# NIRGM_V4.net
KiCad netlist of a schematic drawn in EAGLE
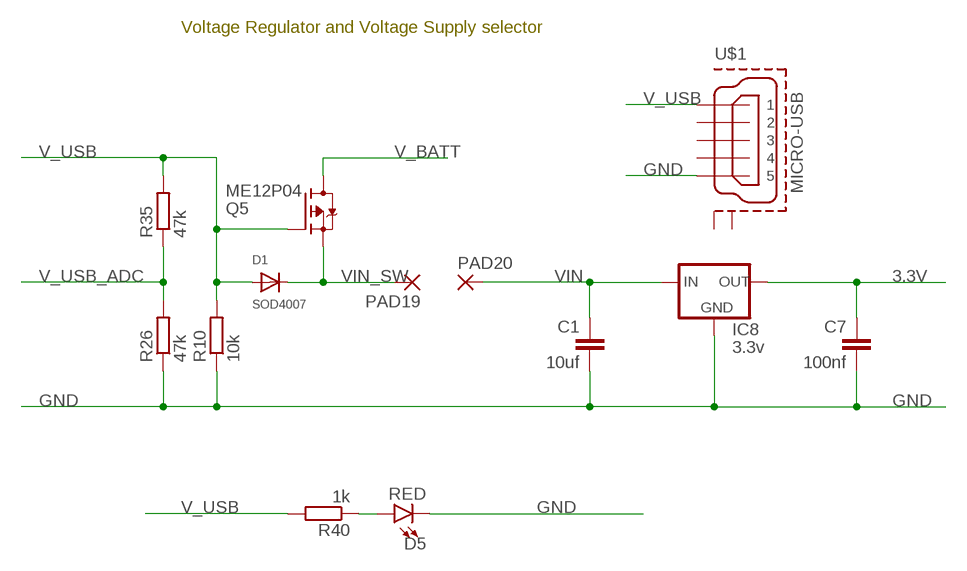
[diagram p0: schematic, sheet 1]
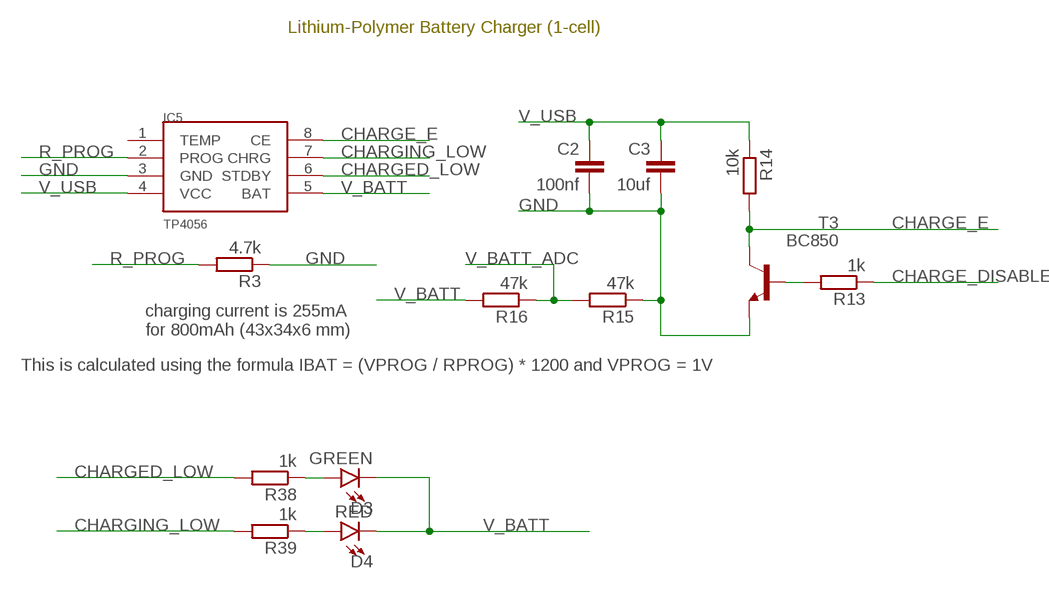
[diagram p1: schematic, sheet 2]
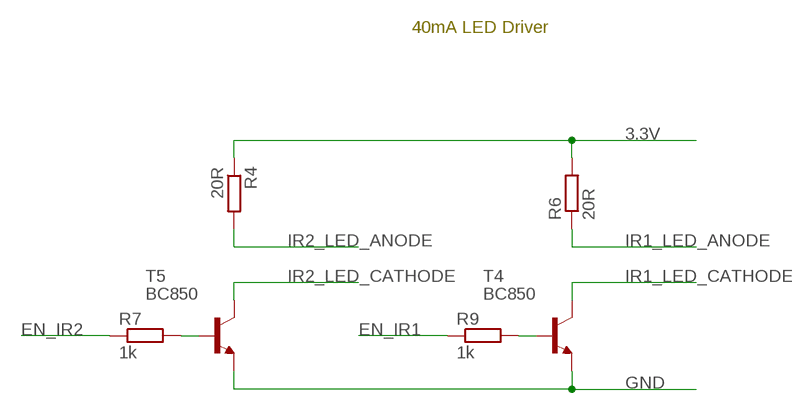
[diagram p2: schematic, sheet 3]
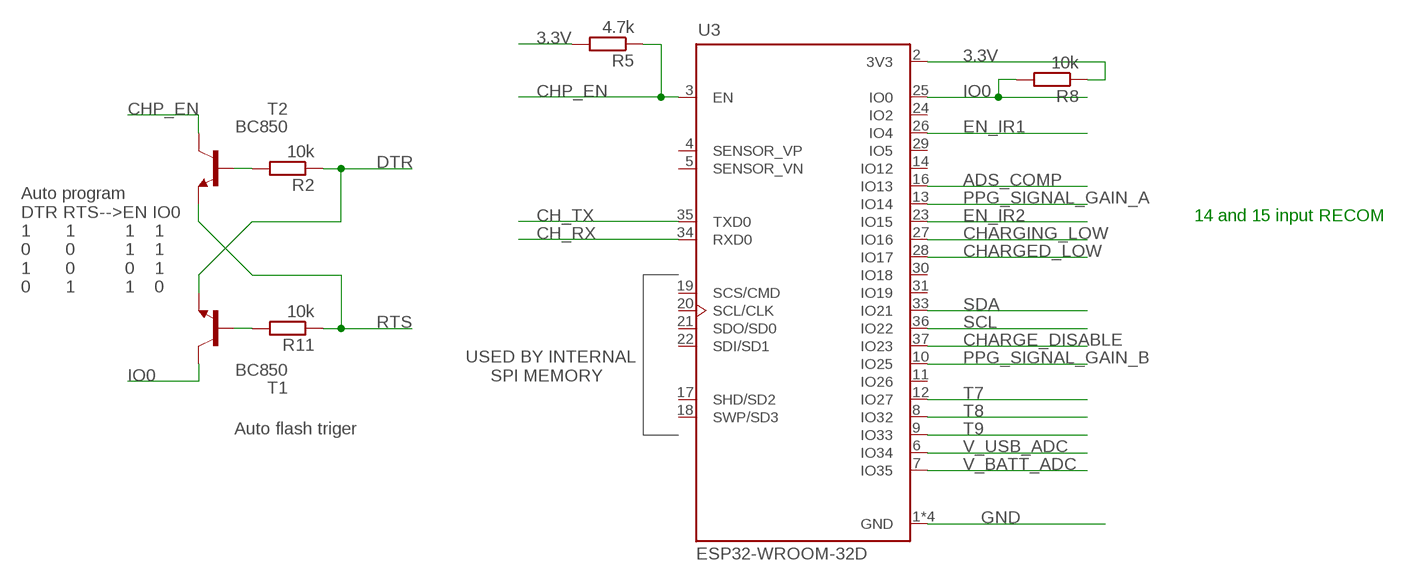
[diagram p3: schematic, sheet 4]
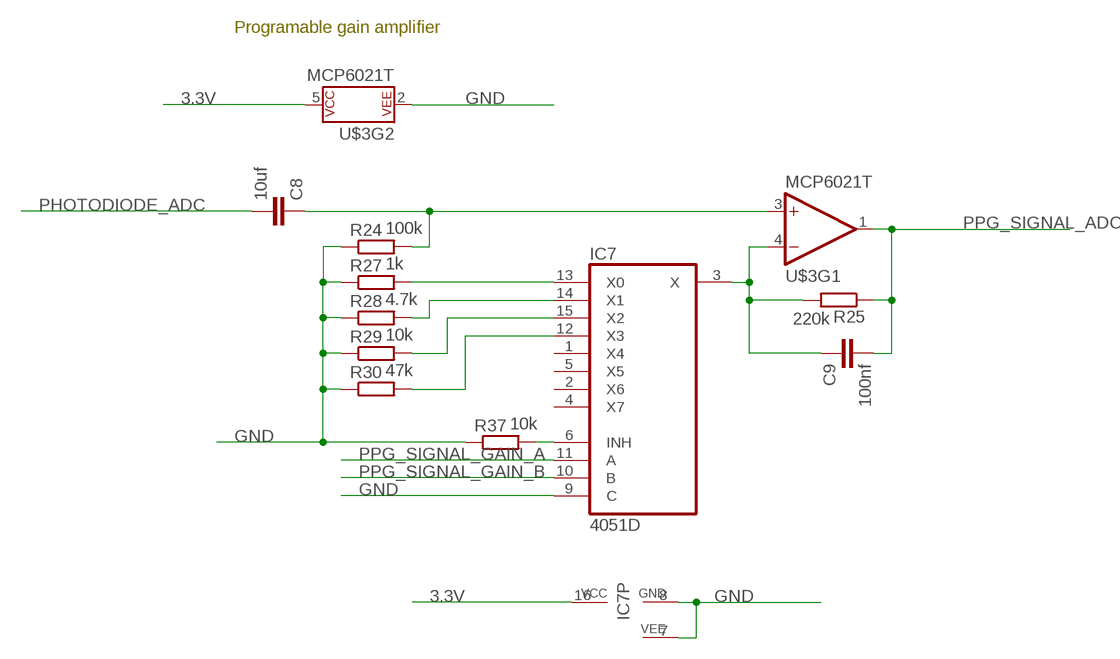
[diagram p4: schematic, sheet 5]
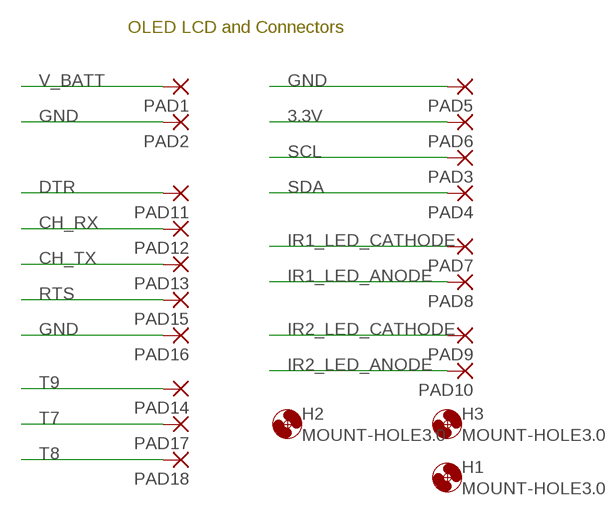
[diagram p5: schematic, sheet 6]
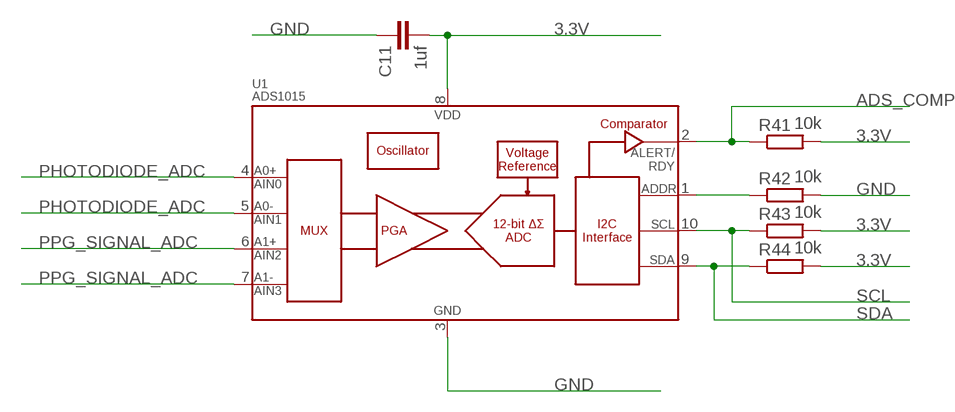
[diagram p6: schematic, sheet 7]
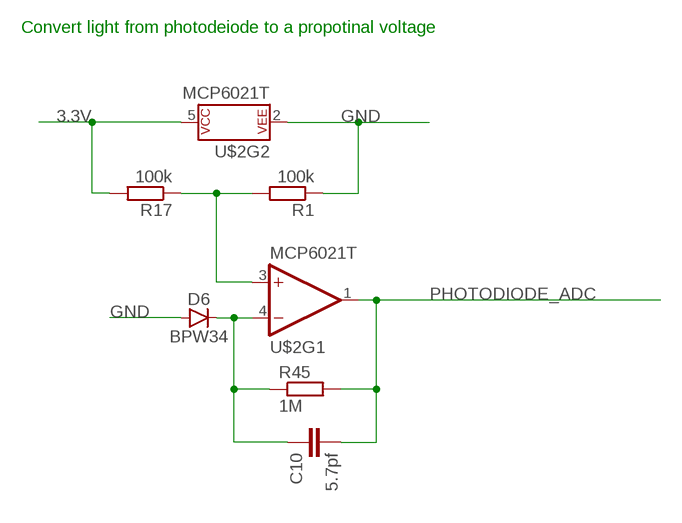
[diagram p7: schematic, sheet 8]

(export (version "E")
  (design (tool "Eeschema 10.0.6"))
  (components
    (comp (ref "H1")
      (value "MOUNT-HOLE3.0")
      (footprint "eagle-import:3,0")
      (libsource (lib "eagle-import") (part "MOUNT-HOLE3.0"))
    )
    (comp (ref "H2")
      (value "MOUNT-HOLE3.0")
      (footprint "eagle-import:3,0")
      (libsource (lib "eagle-import") (part "MOUNT-HOLE3.0"))
    )
    (comp (ref "H3")
      (value "MOUNT-HOLE3.0")
      (footprint "eagle-import:3,0")
      (libsource (lib "eagle-import") (part "MOUNT-HOLE3.0"))
    )
    (comp (ref "PAD1")
      (value "WIREPADSMD5-2,5")
      (footprint "eagle-import:5-2,5")
      (libsource (lib "eagle-import") (part "WIREPADSMD5-2,5"))
    )
    (comp (ref "PAD2")
      (value "WIREPADSMD5-2,5")
      (footprint "eagle-import:5-2,5")
      (libsource (lib "eagle-import") (part "WIREPADSMD5-2,5"))
    )
    (comp (ref "PAD3")
      (value "SMD2")
      (footprint "eagle-import:SMD1,27-2,54")
      (libsource (lib "eagle-import") (part "SMD2"))
    )
    (comp (ref "PAD4")
      (value "SMD2")
      (footprint "eagle-import:SMD1,27-2,54")
      (libsource (lib "eagle-import") (part "SMD2"))
    )
    (comp (ref "PAD5")
      (value "SMD2")
      (footprint "eagle-import:SMD1,27-2,54")
      (libsource (lib "eagle-import") (part "SMD2"))
    )
    (comp (ref "PAD6")
      (value "SMD2")
      (footprint "eagle-import:SMD1,27-2,54")
      (libsource (lib "eagle-import") (part "SMD2"))
    )
    (comp (ref "PAD7")
      (value "SMD2")
      (footprint "eagle-import:SMD1,27-2,54")
      (libsource (lib "eagle-import") (part "SMD2"))
    )
    (comp (ref "PAD8")
      (value "SMD2")
      (footprint "eagle-import:SMD1,27-2,54")
      (libsource (lib "eagle-import") (part "SMD2"))
    )
    (comp (ref "PAD9")
      (value "SMD2")
      (footprint "eagle-import:SMD1,27-2,54")
      (libsource (lib "eagle-import") (part "SMD2"))
    )
    (comp (ref "PAD10")
      (value "SMD2")
      (footprint "eagle-import:SMD1,27-2,54")
      (libsource (lib "eagle-import") (part "SMD2"))
    )
    (comp (ref "PAD11")
      (value "SMD2")
      (footprint "eagle-import:SMD1,27-2,54")
      (libsource (lib "eagle-import") (part "SMD2"))
    )
    (comp (ref "PAD12")
      (value "SMD2")
      (footprint "eagle-import:SMD1,27-2,54")
      (libsource (lib "eagle-import") (part "SMD2"))
    )
    (comp (ref "PAD13")
      (value "SMD2")
      (footprint "eagle-import:SMD1,27-2,54")
      (libsource (lib "eagle-import") (part "SMD2"))
    )
    (comp (ref "PAD14")
      (value "SMD2")
      (footprint "eagle-import:SMD1,27-2,54")
      (libsource (lib "eagle-import") (part "SMD2"))
    )
    (comp (ref "PAD15")
      (value "SMD2")
      (footprint "eagle-import:SMD1,27-2,54")
      (libsource (lib "eagle-import") (part "SMD2"))
    )
    (comp (ref "PAD16")
      (value "SMD2")
      (footprint "eagle-import:SMD1,27-2,54")
      (libsource (lib "eagle-import") (part "SMD2"))
    )
    (comp (ref "PAD17")
      (value "SMD2")
      (footprint "eagle-import:SMD1,27-2,54")
      (libsource (lib "eagle-import") (part "SMD2"))
    )
    (comp (ref "PAD18")
      (value "SMD2")
      (footprint "eagle-import:SMD1,27-2,54")
      (libsource (lib "eagle-import") (part "SMD2"))
    )
    (comp (ref "C1")
      (value "10uf")
      (footprint "eagle-import:C1206K")
      (libsource (lib "eagle-import") (part "C-EUC1206K"))
    )
    (comp (ref "C7")
      (value "100nf")
      (footprint "eagle-import:C1206K")
      (libsource (lib "eagle-import") (part "C-EUC1206K"))
    )
    (comp (ref "D1")
      (value "SOD4007")
      (footprint "eagle-import:SOD-123FL")
      (libsource (lib "eagle-import") (part "DIODE_SOD-123FL"))
    )
    (comp (ref "D5")
      (value "RED")
      (footprint "eagle-import:LED-1206")
      (libsource (lib "eagle-import") (part "LED-GREEN1206"))
    )
    (comp (ref "IC8")
      (value "3.3v")
      (footprint "eagle-import:TO252")
      (libsource (lib "eagle-import") (part "LM1117TO252"))
    )
    (comp (ref "PAD19")
      (value "SMD2")
      (footprint "eagle-import:SMD1,27-2,54")
      (libsource (lib "eagle-import") (part "SMD2"))
    )
    (comp (ref "PAD20")
      (value "SMD2")
      (footprint "eagle-import:SMD1,27-2,54")
      (libsource (lib "eagle-import") (part "SMD2"))
    )
    (comp (ref "Q5")
      (value "ME12P04")
      (footprint "eagle-import:TO252")
      (libsource (lib "eagle-import") (part "FDD4141TO252"))
    )
    (comp (ref "R10")
      (value "10k")
      (footprint "eagle-import:R1206")
      (libsource (lib "eagle-import") (part "R-EU_R1206"))
    )
    (comp (ref "R26")
      (value "47k")
      (footprint "eagle-import:R1206")
      (libsource (lib "eagle-import") (part "R-EU_R1206"))
    )
    (comp (ref "R35")
      (value "47k")
      (footprint "eagle-import:R1206")
      (libsource (lib "eagle-import") (part "R-EU_R1206"))
    )
    (comp (ref "R40")
      (value "1k")
      (footprint "eagle-import:R1206")
      (libsource (lib "eagle-import") (part "R-EU_R1206"))
    )
    (comp (ref "U$1")
      (value "MICRO-USB")
      (footprint "eagle-import:47589-0001")
      (libsource (lib "eagle-import") (part "MICRO-USB-RECEPTACLE47589-0001"))
    )
    (comp (ref "C10")
      (value "5.7pf")
      (footprint "eagle-import:C1206K")
      (libsource (lib "eagle-import") (part "C-EUC1206K"))
    )
    (comp (ref "D6")
      (value "BPW34")
      (footprint "eagle-import:BPW34")
      (libsource (lib "eagle-import") (part "BPW34"))
    )
    (comp (ref "R1")
      (value "100k")
      (footprint "eagle-import:R1206")
      (libsource (lib "eagle-import") (part "R-EU_R1206"))
    )
    (comp (ref "R17")
      (value "100k")
      (footprint "eagle-import:R1206")
      (libsource (lib "eagle-import") (part "R-EU_R1206"))
    )
    (comp (ref "R45")
      (value "1M")
      (footprint "eagle-import:R1206")
      (libsource (lib "eagle-import") (part "R-EU_R1206"))
    )
    (comp (ref "U$2")
      (value "MCP6021T")
      (footprint "eagle-import:SOT23-5")
      (libsource (lib "eagle-import") (part "MCP6021T-E/OT"))
    )
    (comp (ref "C2")
      (value "100nf")
      (footprint "eagle-import:C1206K")
      (libsource (lib "eagle-import") (part "C-EUC1206K"))
    )
    (comp (ref "C3")
      (value "10uf")
      (footprint "eagle-import:C1206K")
      (libsource (lib "eagle-import") (part "C-EUC1206K"))
    )
    (comp (ref "D3")
      (value "GREEN")
      (footprint "eagle-import:LED-1206")
      (libsource (lib "eagle-import") (part "LED-GREEN1206"))
    )
    (comp (ref "D4")
      (value "RED")
      (footprint "eagle-import:LED-1206")
      (libsource (lib "eagle-import") (part "LED-GREEN1206"))
    )
    (comp (ref "IC5")
      (value "TP4056")
      (footprint "eagle-import:SOP-8")
      (libsource (lib "eagle-import") (part "TP4056"))
    )
    (comp (ref "R3")
      (value "4.7k")
      (footprint "eagle-import:R1206")
      (libsource (lib "eagle-import") (part "R-EU_R1206"))
    )
    (comp (ref "R13")
      (value "1k")
      (footprint "eagle-import:R1206")
      (libsource (lib "eagle-import") (part "R-EU_R1206"))
    )
    (comp (ref "R14")
      (value "10k")
      (footprint "eagle-import:R1206")
      (libsource (lib "eagle-import") (part "R-EU_R1206"))
    )
    (comp (ref "R15")
      (value "47k")
      (footprint "eagle-import:R1206")
      (libsource (lib "eagle-import") (part "R-EU_R1206"))
    )
    (comp (ref "R16")
      (value "47k")
      (footprint "eagle-import:R1206")
      (libsource (lib "eagle-import") (part "R-EU_R1206"))
    )
    (comp (ref "R38")
      (value "1k")
      (footprint "eagle-import:R1206")
      (libsource (lib "eagle-import") (part "R-EU_R1206"))
    )
    (comp (ref "R39")
      (value "1k")
      (footprint "eagle-import:R1206")
      (libsource (lib "eagle-import") (part "R-EU_R1206"))
    )
    (comp (ref "T3")
      (value "BC850")
      (footprint "eagle-import:SOT23")
      (libsource (lib "eagle-import") (part "BC850"))
    )
    (comp (ref "C11")
      (value "1uf")
      (footprint "eagle-import:C1206K")
      (libsource (lib "eagle-import") (part "C-EUC1206K"))
    )
    (comp (ref "R41")
      (value "10k")
      (footprint "eagle-import:R1206")
      (libsource (lib "eagle-import") (part "R-EU_R1206"))
    )
    (comp (ref "R42")
      (value "10k")
      (footprint "eagle-import:R1206")
      (libsource (lib "eagle-import") (part "R-EU_R1206"))
    )
    (comp (ref "R43")
      (value "10k")
      (footprint "eagle-import:R1206")
      (libsource (lib "eagle-import") (part "R-EU_R1206"))
    )
    (comp (ref "R44")
      (value "10k")
      (footprint "eagle-import:R1206")
      (libsource (lib "eagle-import") (part "R-EU_R1206"))
    )
    (comp (ref "U1")
      (value "ADS1015")
      (footprint "eagle-import:MSOP10")
      (libsource (lib "eagle-import") (part "ADS1015"))
    )
    (comp (ref "R2")
      (value "10k")
      (footprint "eagle-import:R1206")
      (libsource (lib "eagle-import") (part "R-EU_R1206"))
    )
    (comp (ref "R5")
      (value "4.7k")
      (footprint "eagle-import:R1206")
      (libsource (lib "eagle-import") (part "R-EU_R1206"))
    )
    (comp (ref "R8")
      (value "10k")
      (footprint "eagle-import:R1206")
      (libsource (lib "eagle-import") (part "R-EU_R1206"))
    )
    (comp (ref "R11")
      (value "10k")
      (footprint "eagle-import:R1206")
      (libsource (lib "eagle-import") (part "R-EU_R1206"))
    )
    (comp (ref "T1")
      (value "BC850")
      (footprint "eagle-import:SOT23")
      (libsource (lib "eagle-import") (part "BC850"))
    )
    (comp (ref "T2")
      (value "BC850")
      (footprint "eagle-import:SOT23")
      (libsource (lib "eagle-import") (part "BC850"))
    )
    (comp (ref "U3")
      (value "ESP32-WROOM-32D")
      (footprint "eagle-import:MODULE_ESP32-WROOM-32D")
      (fields (field (name "MF") "Espressif Systems"))
      (libsource (lib "eagle-import") (part "ESP32-WROOM-32D"))
    )
    (comp (ref "R4")
      (value "20R")
      (footprint "eagle-import:R1206")
      (libsource (lib "eagle-import") (part "R-EU_R1206"))
    )
    (comp (ref "R6")
      (value "20R")
      (footprint "eagle-import:R1206")
      (libsource (lib "eagle-import") (part "R-EU_R1206"))
    )
    (comp (ref "R7")
      (value "1k")
      (footprint "eagle-import:R1206")
      (libsource (lib "eagle-import") (part "R-EU_R1206"))
    )
    (comp (ref "R9")
      (value "1k")
      (footprint "eagle-import:R1206")
      (libsource (lib "eagle-import") (part "R-EU_R1206"))
    )
    (comp (ref "T4")
      (value "BC850")
      (footprint "eagle-import:SOT23")
      (libsource (lib "eagle-import") (part "BC850"))
    )
    (comp (ref "T5")
      (value "BC850")
      (footprint "eagle-import:SOT23")
      (libsource (lib "eagle-import") (part "BC850"))
    )
    (comp (ref "C8")
      (value "10uf")
      (footprint "eagle-import:C1206K")
      (libsource (lib "eagle-import") (part "C-EUC1206K"))
    )
    (comp (ref "C9")
      (value "100nf")
      (footprint "eagle-import:C1206K")
      (libsource (lib "eagle-import") (part "C-EUC1206K"))
    )
    (comp (ref "IC7")
      (value "4051D")
      (footprint "eagle-import:SO16")
      (libsource (lib "eagle-import") (part "4051D"))
    )
    (comp (ref "R24")
      (value "100k")
      (footprint "eagle-import:R1206")
      (libsource (lib "eagle-import") (part "R-EU_R1206"))
    )
    (comp (ref "R25")
      (value "220k")
      (footprint "eagle-import:R1206")
      (libsource (lib "eagle-import") (part "R-EU_R1206"))
    )
    (comp (ref "R27")
      (value "1k")
      (footprint "eagle-import:R1206")
      (libsource (lib "eagle-import") (part "R-EU_R1206"))
    )
    (comp (ref "R28")
      (value "4.7k")
      (footprint "eagle-import:R1206")
      (libsource (lib "eagle-import") (part "R-EU_R1206"))
    )
    (comp (ref "R29")
      (value "10k")
      (footprint "eagle-import:R1206")
      (libsource (lib "eagle-import") (part "R-EU_R1206"))
    )
    (comp (ref "R30")
      (value "47k")
      (footprint "eagle-import:R1206")
      (libsource (lib "eagle-import") (part "R-EU_R1206"))
    )
    (comp (ref "R37")
      (value "10k")
      (footprint "eagle-import:R1206")
      (libsource (lib "eagle-import") (part "R-EU_R1206"))
    )
    (comp (ref "U$3")
      (value "MCP6021T")
      (footprint "eagle-import:SOT23-5")
      (libsource (lib "eagle-import") (part "MCP6021T-E/OT"))
    )
  )
  (nets
    (net (code "1") (name "3.3V") (class "Default")
      (node (ref "C11") (pin "2") (pinfunction "2_2") (pintype "passive"))
      (node (ref "C7") (pin "1") (pinfunction "1_1") (pintype "passive"))
      (node (ref "IC7") (pin "16") (pinfunction "VCC_16") (pintype "power_in"))
      (node (ref "IC8") (pin "3") (pinfunction "OUT_3") (pintype "passive"))
      (node (ref "PAD6") (pin "1") (pinfunction "P_1") (pintype "passive"))
      (node (ref "R17") (pin "2") (pinfunction "2_2") (pintype "passive"))
      (node (ref "R4") (pin "1") (pinfunction "1_1") (pintype "passive"))
      (node (ref "R41") (pin "2") (pinfunction "2_2") (pintype "passive"))
      (node (ref "R43") (pin "2") (pinfunction "2_2") (pintype "passive"))
      (node (ref "R44") (pin "2") (pinfunction "2_2") (pintype "passive"))
      (node (ref "R5") (pin "2") (pinfunction "2_2") (pintype "passive"))
      (node (ref "R6") (pin "2") (pinfunction "2_2") (pintype "passive"))
      (node (ref "R8") (pin "1") (pinfunction "1_1") (pintype "passive"))
      (node (ref "U$2") (pin "5") (pinfunction "P$V+_5") (pintype "bidirectional"))
      (node (ref "U$3") (pin "5") (pinfunction "P$V+_5") (pintype "bidirectional"))
      (node (ref "U1") (pin "8") (pinfunction "VDD_8") (pintype "bidirectional"))
      (node (ref "U3") (pin "2") (pinfunction "3V3_2") (pintype "power_in"))
    )
    (net (code "2") (name "ADS_COMP") (class "Default")
      (node (ref "R41") (pin "1") (pinfunction "1_1") (pintype "passive"))
      (node (ref "U1") (pin "2") (pinfunction "ALERT/RDY_2") (pintype "bidirectional"))
      (node (ref "U3") (pin "16") (pinfunction "IO13_16") (pintype "bidirectional"))
    )
    (net (code "3") (name "CHARGED_LOW") (class "Default")
      (node (ref "IC5") (pin "6") (pinfunction "STDBY_6") (pintype "bidirectional"))
      (node (ref "R38") (pin "2") (pinfunction "2_2") (pintype "passive"))
      (node (ref "U3") (pin "28") (pinfunction "IO17_28") (pintype "bidirectional"))
    )
    (net (code "4") (name "CHARGE_DISABLE") (class "Default")
      (node (ref "R13") (pin "1") (pinfunction "1_1") (pintype "passive"))
      (node (ref "U3") (pin "37") (pinfunction "IO23_37") (pintype "bidirectional"))
    )
    (net (code "5") (name "CHARGE_E") (class "Default")
      (node (ref "IC5") (pin "8") (pinfunction "CE_8") (pintype "bidirectional"))
      (node (ref "R14") (pin "2") (pinfunction "2_2") (pintype "passive"))
      (node (ref "T3") (pin "3") (pinfunction "C_3") (pintype "passive"))
    )
    (net (code "6") (name "CHARGING_LOW") (class "Default")
      (node (ref "IC5") (pin "7") (pinfunction "CHRG_7") (pintype "bidirectional"))
      (node (ref "R39") (pin "2") (pinfunction "2_2") (pintype "passive"))
      (node (ref "U3") (pin "27") (pinfunction "IO16_27") (pintype "bidirectional"))
    )
    (net (code "7") (name "CHP_EN") (class "Default")
      (node (ref "R5") (pin "1") (pinfunction "1_1") (pintype "passive"))
      (node (ref "T2") (pin "3") (pinfunction "C_3") (pintype "passive"))
      (node (ref "U3") (pin "3") (pinfunction "EN_3") (pintype "input"))
    )
    (net (code "8") (name "CH_RX") (class "Default")
      (node (ref "PAD12") (pin "1") (pinfunction "P_1") (pintype "passive"))
      (node (ref "U3") (pin "34") (pinfunction "RXD0_34") (pintype "bidirectional"))
    )
    (net (code "9") (name "CH_TX") (class "Default")
      (node (ref "PAD13") (pin "1") (pinfunction "P_1") (pintype "passive"))
      (node (ref "U3") (pin "35") (pinfunction "TXD0_35") (pintype "bidirectional"))
    )
    (net (code "10") (name "DTR") (class "Default")
      (node (ref "PAD11") (pin "1") (pinfunction "P_1") (pintype "passive"))
      (node (ref "R2") (pin "1") (pinfunction "1_1") (pintype "passive"))
      (node (ref "T1") (pin "2") (pinfunction "E_2") (pintype "passive"))
    )
    (net (code "11") (name "EN_IR1") (class "Default")
      (node (ref "R9") (pin "1") (pinfunction "1_1") (pintype "passive"))
      (node (ref "U3") (pin "26") (pinfunction "IO4_26") (pintype "bidirectional"))
    )
    (net (code "12") (name "EN_IR2") (class "Default")
      (node (ref "R7") (pin "1") (pinfunction "1_1") (pintype "passive"))
      (node (ref "U3") (pin "23") (pinfunction "IO15_23") (pintype "bidirectional"))
    )
    (net (code "13") (name "GND") (class "Default")
      (node (ref "C1") (pin "2") (pinfunction "2_2") (pintype "passive"))
      (node (ref "C11") (pin "1") (pinfunction "1_1") (pintype "passive"))
      (node (ref "C2") (pin "2") (pinfunction "2_2") (pintype "passive"))
      (node (ref "C3") (pin "2") (pinfunction "2_2") (pintype "passive"))
      (node (ref "C7") (pin "2") (pinfunction "2_2") (pintype "passive"))
      (node (ref "D5") (pin "C") (pinfunction "C_C") (pintype "passive"))
      (node (ref "D6") (pin "P$1") (pinfunction "A_P$1") (pintype "passive"))
      (node (ref "IC5") (pin "3") (pinfunction "GND_3") (pintype "bidirectional"))
      (node (ref "IC7") (pin "7") (pinfunction "VEE_7") (pintype "power_in"))
      (node (ref "IC7") (pin "8") (pinfunction "GND_8") (pintype "power_in"))
      (node (ref "IC7") (pin "9") (pinfunction "C_9") (pintype "input"))
      (node (ref "IC8") (pin "1") (pinfunction "GND_1") (pintype "input"))
      (node (ref "PAD16") (pin "1") (pinfunction "P_1") (pintype "passive"))
      (node (ref "PAD2") (pin "1") (pinfunction "P_1") (pintype "passive"))
      (node (ref "PAD5") (pin "1") (pinfunction "P_1") (pintype "passive"))
      (node (ref "R1") (pin "1") (pinfunction "1_1") (pintype "passive"))
      (node (ref "R10") (pin "1") (pinfunction "1_1") (pintype "passive"))
      (node (ref "R15") (pin "1") (pinfunction "1_1") (pintype "passive"))
      (node (ref "R24") (pin "1") (pinfunction "1_1") (pintype "passive"))
      (node (ref "R26") (pin "1") (pinfunction "1_1") (pintype "passive"))
      (node (ref "R27") (pin "1") (pinfunction "1_1") (pintype "passive"))
      (node (ref "R28") (pin "1") (pinfunction "1_1") (pintype "passive"))
      (node (ref "R29") (pin "1") (pinfunction "1_1") (pintype "passive"))
      (node (ref "R3") (pin "1") (pinfunction "1_1") (pintype "passive"))
      (node (ref "R30") (pin "1") (pinfunction "1_1") (pintype "passive"))
      (node (ref "R37") (pin "1") (pinfunction "1_1") (pintype "passive"))
      (node (ref "R42") (pin "2") (pinfunction "2_2") (pintype "passive"))
      (node (ref "T3") (pin "2") (pinfunction "E_2") (pintype "passive"))
      (node (ref "T4") (pin "2") (pinfunction "E_2") (pintype "passive"))
      (node (ref "T5") (pin "2") (pinfunction "E_2") (pintype "passive"))
      (node (ref "U$1") (pin "5") (pinfunction "5_5") (pintype "input"))
      (node (ref "U$2") (pin "2") (pinfunction "P$V-_2") (pintype "bidirectional"))
      (node (ref "U$3") (pin "2") (pinfunction "P$V-_2") (pintype "bidirectional"))
      (node (ref "U1") (pin "3") (pinfunction "VSS_3") (pintype "bidirectional"))
      (node (ref "U3") (pin "1") (pinfunction "GND_1") (pintype "power_in"))
      (node (ref "U3") (pin "15") (pinfunction "GND_15") (pintype "power_in"))
      (node (ref "U3") (pin "38") (pinfunction "GND_38") (pintype "power_in"))
      (node (ref "U3") (pin "39") (pinfunction "GND_39") (pintype "power_in"))
    )
    (net (code "14") (name "IO0") (class "Default")
      (node (ref "R8") (pin "2") (pinfunction "2_2") (pintype "passive"))
      (node (ref "T1") (pin "3") (pinfunction "C_3") (pintype "passive"))
      (node (ref "U3") (pin "25") (pinfunction "IO0_25") (pintype "bidirectional"))
    )
    (net (code "15") (name "IR1_LED_ANODE") (class "Default")
      (node (ref "PAD8") (pin "1") (pinfunction "P_1") (pintype "passive"))
      (node (ref "R6") (pin "1") (pinfunction "1_1") (pintype "passive"))
    )
    (net (code "16") (name "IR1_LED_CATHODE") (class "Default")
      (node (ref "PAD7") (pin "1") (pinfunction "P_1") (pintype "passive"))
      (node (ref "T4") (pin "3") (pinfunction "C_3") (pintype "passive"))
    )
    (net (code "17") (name "IR2_LED_ANODE") (class "Default")
      (node (ref "PAD10") (pin "1") (pinfunction "P_1") (pintype "passive"))
      (node (ref "R4") (pin "2") (pinfunction "2_2") (pintype "passive"))
    )
    (net (code "18") (name "IR2_LED_CATHODE") (class "Default")
      (node (ref "PAD9") (pin "1") (pinfunction "P_1") (pintype "passive"))
      (node (ref "T5") (pin "3") (pinfunction "C_3") (pintype "passive"))
    )
    (net (code "19") (name "Net-(D3-PadA)") (class "Default")
      (node (ref "D3") (pin "A") (pinfunction "A_A") (pintype "passive"))
      (node (ref "R38") (pin "1") (pinfunction "1_1") (pintype "passive"))
    )
    (net (code "20") (name "Net-(D4-PadA)") (class "Default")
      (node (ref "D4") (pin "A") (pinfunction "A_A") (pintype "passive"))
      (node (ref "R39") (pin "1") (pinfunction "1_1") (pintype "passive"))
    )
    (net (code "21") (name "Net-(D5-PadA)") (class "Default")
      (node (ref "D5") (pin "A") (pinfunction "A_A") (pintype "passive"))
      (node (ref "R40") (pin "1") (pinfunction "1_1") (pintype "passive"))
    )
    (net (code "22") (name "Net-(D6-C)") (class "Default")
      (node (ref "C10") (pin "1") (pinfunction "1_1") (pintype "passive"))
      (node (ref "D6") (pin "P$2") (pinfunction "C_P$2") (pintype "passive"))
      (node (ref "R45") (pin "1") (pinfunction "1_1") (pintype "passive"))
      (node (ref "U$2") (pin "4") (pinfunction "-IN_4") (pintype "input"))
    )
    (net (code "23") (name "Net-(IC7A-INH)") (class "Default")
      (node (ref "IC7") (pin "6") (pinfunction "INH_6") (pintype "input"))
      (node (ref "R37") (pin "2") (pinfunction "2_2") (pintype "passive"))
    )
    (net (code "24") (name "Net-(IC7A-X)") (class "Default")
      (node (ref "C9") (pin "1") (pinfunction "1_1") (pintype "passive"))
      (node (ref "IC7") (pin "3") (pinfunction "X_3") (pintype "bidirectional"))
      (node (ref "R25") (pin "2") (pinfunction "2_2") (pintype "passive"))
      (node (ref "U$3") (pin "4") (pinfunction "-IN_4") (pintype "input"))
    )
    (net (code "25") (name "Net-(IC7A-X0)") (class "Default")
      (node (ref "IC7") (pin "13") (pinfunction "X0_13") (pintype "bidirectional"))
      (node (ref "R27") (pin "2") (pinfunction "2_2") (pintype "passive"))
    )
    (net (code "26") (name "Net-(IC7A-X1)") (class "Default")
      (node (ref "IC7") (pin "14") (pinfunction "X1_14") (pintype "bidirectional"))
      (node (ref "R28") (pin "2") (pinfunction "2_2") (pintype "passive"))
    )
    (net (code "27") (name "Net-(IC7A-X2)") (class "Default")
      (node (ref "IC7") (pin "15") (pinfunction "X2_15") (pintype "bidirectional"))
      (node (ref "R29") (pin "2") (pinfunction "2_2") (pintype "passive"))
    )
    (net (code "28") (name "Net-(IC7A-X3)") (class "Default")
      (node (ref "IC7") (pin "12") (pinfunction "X3_12") (pintype "bidirectional"))
      (node (ref "R30") (pin "2") (pinfunction "2_2") (pintype "passive"))
    )
    (net (code "29") (name "Net-(T1-B)") (class "Default")
      (node (ref "R11") (pin "2") (pinfunction "2_2") (pintype "passive"))
      (node (ref "T1") (pin "1") (pinfunction "B_1") (pintype "passive"))
    )
    (net (code "30") (name "Net-(T2-B)") (class "Default")
      (node (ref "R2") (pin "2") (pinfunction "2_2") (pintype "passive"))
      (node (ref "T2") (pin "1") (pinfunction "B_1") (pintype "passive"))
    )
    (net (code "31") (name "Net-(T3-B)") (class "Default")
      (node (ref "R13") (pin "2") (pinfunction "2_2") (pintype "passive"))
      (node (ref "T3") (pin "1") (pinfunction "B_1") (pintype "passive"))
    )
    (net (code "32") (name "Net-(T4-B)") (class "Default")
      (node (ref "R9") (pin "2") (pinfunction "2_2") (pintype "passive"))
      (node (ref "T4") (pin "1") (pinfunction "B_1") (pintype "passive"))
    )
    (net (code "33") (name "Net-(T5-B)") (class "Default")
      (node (ref "R7") (pin "2") (pinfunction "2_2") (pintype "passive"))
      (node (ref "T5") (pin "1") (pinfunction "B_1") (pintype "passive"))
    )
    (net (code "34") (name "Net-(U$2A-+IN)") (class "Default")
      (node (ref "R1") (pin "2") (pinfunction "2_2") (pintype "passive"))
      (node (ref "R17") (pin "1") (pinfunction "1_1") (pintype "passive"))
      (node (ref "U$2") (pin "3") (pinfunction "+IN_3") (pintype "input"))
    )
    (net (code "35") (name "Net-(U$3A-+IN)") (class "Default")
      (node (ref "C8") (pin "1") (pinfunction "1_1") (pintype "passive"))
      (node (ref "R24") (pin "2") (pinfunction "2_2") (pintype "passive"))
      (node (ref "U$3") (pin "3") (pinfunction "+IN_3") (pintype "input"))
    )
    (net (code "36") (name "Net-(U1-ADDR)") (class "Default")
      (node (ref "R42") (pin "1") (pinfunction "1_1") (pintype "passive"))
      (node (ref "U1") (pin "1") (pinfunction "ADDR_1") (pintype "bidirectional"))
    )
    (net (code "37") (name "PHOTODIODE_ADC") (class "Default")
      (node (ref "C10") (pin "2") (pinfunction "2_2") (pintype "passive"))
      (node (ref "C8") (pin "2") (pinfunction "2_2") (pintype "passive"))
      (node (ref "R45") (pin "2") (pinfunction "2_2") (pintype "passive"))
      (node (ref "U$2") (pin "1") (pinfunction "OUT_1") (pintype "output"))
      (node (ref "U1") (pin "4") (pinfunction "AIN0_4") (pintype "bidirectional"))
      (node (ref "U1") (pin "5") (pinfunction "AIN1_5") (pintype "bidirectional"))
    )
    (net (code "38") (name "PPG_SIGNAL_ADC") (class "Default")
      (node (ref "C9") (pin "2") (pinfunction "2_2") (pintype "passive"))
      (node (ref "R25") (pin "1") (pinfunction "1_1") (pintype "passive"))
      (node (ref "U$3") (pin "1") (pinfunction "OUT_1") (pintype "output"))
      (node (ref "U1") (pin "6") (pinfunction "AIN2_6") (pintype "bidirectional"))
      (node (ref "U1") (pin "7") (pinfunction "AIN3_7") (pintype "bidirectional"))
    )
    (net (code "39") (name "PPG_SIGNAL_GAIN_A") (class "Default")
      (node (ref "IC7") (pin "11") (pinfunction "A_11") (pintype "input"))
      (node (ref "U3") (pin "13") (pinfunction "IO14_13") (pintype "bidirectional"))
    )
    (net (code "40") (name "PPG_SIGNAL_GAIN_B") (class "Default")
      (node (ref "IC7") (pin "10") (pinfunction "B_10") (pintype "input"))
      (node (ref "U3") (pin "10") (pinfunction "IO25_10") (pintype "bidirectional"))
    )
    (net (code "41") (name "RTS") (class "Default")
      (node (ref "PAD15") (pin "1") (pinfunction "P_1") (pintype "passive"))
      (node (ref "R11") (pin "1") (pinfunction "1_1") (pintype "passive"))
      (node (ref "T2") (pin "2") (pinfunction "E_2") (pintype "passive"))
    )
    (net (code "42") (name "R_PROG") (class "Default")
      (node (ref "IC5") (pin "2") (pinfunction "PROG_2") (pintype "bidirectional"))
      (node (ref "R3") (pin "2") (pinfunction "2_2") (pintype "passive"))
    )
    (net (code "43") (name "SCL") (class "Default")
      (node (ref "PAD3") (pin "1") (pinfunction "P_1") (pintype "passive"))
      (node (ref "R43") (pin "1") (pinfunction "1_1") (pintype "passive"))
      (node (ref "U1") (pin "10") (pinfunction "SCL_10") (pintype "bidirectional"))
      (node (ref "U3") (pin "36") (pinfunction "IO22_36") (pintype "bidirectional"))
    )
    (net (code "44") (name "SDA") (class "Default")
      (node (ref "PAD4") (pin "1") (pinfunction "P_1") (pintype "passive"))
      (node (ref "R44") (pin "1") (pinfunction "1_1") (pintype "passive"))
      (node (ref "U1") (pin "9") (pinfunction "SDA_9") (pintype "bidirectional"))
      (node (ref "U3") (pin "33") (pinfunction "IO21_33") (pintype "bidirectional"))
    )
    (net (code "45") (name "T7") (class "Default")
      (node (ref "PAD17") (pin "1") (pinfunction "P_1") (pintype "passive"))
      (node (ref "U3") (pin "12") (pinfunction "IO27_12") (pintype "bidirectional"))
    )
    (net (code "46") (name "T8") (class "Default")
      (node (ref "PAD18") (pin "1") (pinfunction "P_1") (pintype "passive"))
      (node (ref "U3") (pin "8") (pinfunction "IO32_8") (pintype "bidirectional"))
    )
    (net (code "47") (name "T9") (class "Default")
      (node (ref "PAD14") (pin "1") (pinfunction "P_1") (pintype "passive"))
      (node (ref "U3") (pin "9") (pinfunction "IO33_9") (pintype "bidirectional"))
    )
    (net (code "48") (name "VIN") (class "Default")
      (node (ref "C1") (pin "1") (pinfunction "1_1") (pintype "passive"))
      (node (ref "IC8") (pin "2") (pinfunction "IN_2") (pintype "input"))
      (node (ref "PAD20") (pin "1") (pinfunction "P_1") (pintype "passive"))
    )
    (net (code "49") (name "VIN_SW") (class "Default")
      (node (ref "D1") (pin "C") (pinfunction "C_C") (pintype "passive"))
      (node (ref "PAD19") (pin "1") (pinfunction "P_1") (pintype "passive"))
      (node (ref "Q5") (pin "2") (pinfunction "S_2") (pintype "passive"))
    )
    (net (code "50") (name "V_BATT") (class "Default")
      (node (ref "D3") (pin "C") (pinfunction "C_C") (pintype "passive"))
      (node (ref "D4") (pin "C") (pinfunction "C_C") (pintype "passive"))
      (node (ref "IC5") (pin "5") (pinfunction "BAT_5") (pintype "bidirectional"))
      (node (ref "PAD1") (pin "1") (pinfunction "P_1") (pintype "passive"))
      (node (ref "Q5") (pin "3") (pinfunction "D_3") (pintype "passive"))
      (node (ref "R16") (pin "2") (pinfunction "2_2") (pintype "passive"))
    )
    (net (code "51") (name "V_BATT_ADC") (class "Default")
      (node (ref "R15") (pin "2") (pinfunction "2_2") (pintype "passive"))
      (node (ref "R16") (pin "1") (pinfunction "1_1") (pintype "passive"))
      (node (ref "U3") (pin "7") (pinfunction "IO35_7") (pintype "bidirectional"))
    )
    (net (code "52") (name "V_USB") (class "Default")
      (node (ref "C2") (pin "1") (pinfunction "1_1") (pintype "passive"))
      (node (ref "C3") (pin "1") (pinfunction "1_1") (pintype "passive"))
      (node (ref "D1") (pin "A") (pinfunction "A_A") (pintype "passive"))
      (node (ref "IC5") (pin "4") (pinfunction "VCC_4") (pintype "bidirectional"))
      (node (ref "Q5") (pin "1") (pinfunction "G_1") (pintype "passive"))
      (node (ref "R10") (pin "2") (pinfunction "2_2") (pintype "passive"))
      (node (ref "R14") (pin "1") (pinfunction "1_1") (pintype "passive"))
      (node (ref "R35") (pin "2") (pinfunction "2_2") (pintype "passive"))
      (node (ref "R40") (pin "2") (pinfunction "2_2") (pintype "passive"))
      (node (ref "U$1") (pin "1") (pinfunction "1_1") (pintype "input"))
    )
    (net (code "53") (name "V_USB_ADC") (class "Default")
      (node (ref "R26") (pin "2") (pinfunction "2_2") (pintype "passive"))
      (node (ref "R35") (pin "1") (pinfunction "1_1") (pintype "passive"))
      (node (ref "U3") (pin "6") (pinfunction "IO34_6") (pintype "bidirectional"))
    )
    (net (code "54") (name "unconnected-(IC5-TEMP-Pad1)") (class "Default")
      (node (ref "IC5") (pin "1") (pinfunction "TEMP_1") (pintype "bidirectional"))
    )
    (net (code "55") (name "unconnected-(IC7A-X4-Pad1)") (class "Default")
      (node (ref "IC7") (pin "1") (pinfunction "X4_1") (pintype "bidirectional"))
    )
    (net (code "56") (name "unconnected-(IC7A-X5-Pad5)") (class "Default")
      (node (ref "IC7") (pin "5") (pinfunction "X5_5") (pintype "bidirectional"))
    )
    (net (code "57") (name "unconnected-(IC7A-X6-Pad2)") (class "Default")
      (node (ref "IC7") (pin "2") (pinfunction "X6_2") (pintype "bidirectional"))
    )
    (net (code "58") (name "unconnected-(IC7A-X7-Pad4)") (class "Default")
      (node (ref "IC7") (pin "4") (pinfunction "X7_4") (pintype "bidirectional"))
    )
    (net (code "59") (name "unconnected-(U$1-GND1-PadP$1)") (class "Default")
      (node (ref "U$1") (pin "P$1") (pinfunction "GND1_P$1") (pintype "bidirectional"))
    )
    (net (code "60") (name "unconnected-(U$1-GND2-PadP$2)") (class "Default")
      (node (ref "U$1") (pin "P$2") (pinfunction "GND2_P$2") (pintype "bidirectional"))
    )
    (net (code "61") (name "unconnected-(U$1-Pad2)") (class "Default")
      (node (ref "U$1") (pin "2") (pinfunction "2_2") (pintype "input"))
    )
    (net (code "62") (name "unconnected-(U$1-Pad3)") (class "Default")
      (node (ref "U$1") (pin "3") (pinfunction "3_3") (pintype "input"))
    )
    (net (code "63") (name "unconnected-(U$1-Pad4)") (class "Default")
      (node (ref "U$1") (pin "4") (pinfunction "4_4") (pintype "input"))
    )
    (net (code "64") (name "unconnected-(U3-IO2-Pad24)") (class "Default")
      (node (ref "U3") (pin "24") (pinfunction "IO2_24") (pintype "bidirectional"))
    )
    (net (code "65") (name "unconnected-(U3-IO5-Pad29)") (class "Default")
      (node (ref "U3") (pin "29") (pinfunction "IO5_29") (pintype "bidirectional"))
    )
    (net (code "66") (name "unconnected-(U3-IO12-Pad14)") (class "Default")
      (node (ref "U3") (pin "14") (pinfunction "IO12_14") (pintype "bidirectional"))
    )
    (net (code "67") (name "unconnected-(U3-IO18-Pad30)") (class "Default")
      (node (ref "U3") (pin "30") (pinfunction "IO18_30") (pintype "bidirectional"))
    )
    (net (code "68") (name "unconnected-(U3-IO19-Pad31)") (class "Default")
      (node (ref "U3") (pin "31") (pinfunction "IO19_31") (pintype "bidirectional"))
    )
    (net (code "69") (name "unconnected-(U3-IO26-Pad11)") (class "Default")
      (node (ref "U3") (pin "11") (pinfunction "IO26_11") (pintype "bidirectional"))
    )
    (net (code "70") (name "unconnected-(U3-SCL{slash}CLK-Pad20)") (class "Default")
      (node (ref "U3") (pin "20") (pinfunction "SCL/CLK_20") (pintype "bidirectional"))
    )
    (net (code "71") (name "unconnected-(U3-SCS{slash}CMD-Pad19)") (class "Default")
      (node (ref "U3") (pin "19") (pinfunction "SCS/CMD_19") (pintype "bidirectional"))
    )
    (net (code "72") (name "unconnected-(U3-SDI{slash}SD1-Pad22)") (class "Default")
      (node (ref "U3") (pin "22") (pinfunction "SDI/SD1_22") (pintype "bidirectional"))
    )
    (net (code "73") (name "unconnected-(U3-SDO{slash}SD0-Pad21)") (class "Default")
      (node (ref "U3") (pin "21") (pinfunction "SDO/SD0_21") (pintype "bidirectional"))
    )
    (net (code "74") (name "unconnected-(U3-SENSOR_VN-Pad5)") (class "Default")
      (node (ref "U3") (pin "5") (pinfunction "SENSOR_VN_5") (pintype "input"))
    )
    (net (code "75") (name "unconnected-(U3-SENSOR_VP-Pad4)") (class "Default")
      (node (ref "U3") (pin "4") (pinfunction "SENSOR_VP_4") (pintype "input"))
    )
    (net (code "76") (name "unconnected-(U3-SHD{slash}SD2-Pad17)") (class "Default")
      (node (ref "U3") (pin "17") (pinfunction "SHD/SD2_17") (pintype "bidirectional"))
    )
    (net (code "77") (name "unconnected-(U3-SWP{slash}SD3-Pad18)") (class "Default")
      (node (ref "U3") (pin "18") (pinfunction "SWP/SD3_18") (pintype "bidirectional"))
    )
  )
)
